# BDAN_TFT.net
KiCad netlist of a schematic drawn in Altium Designer
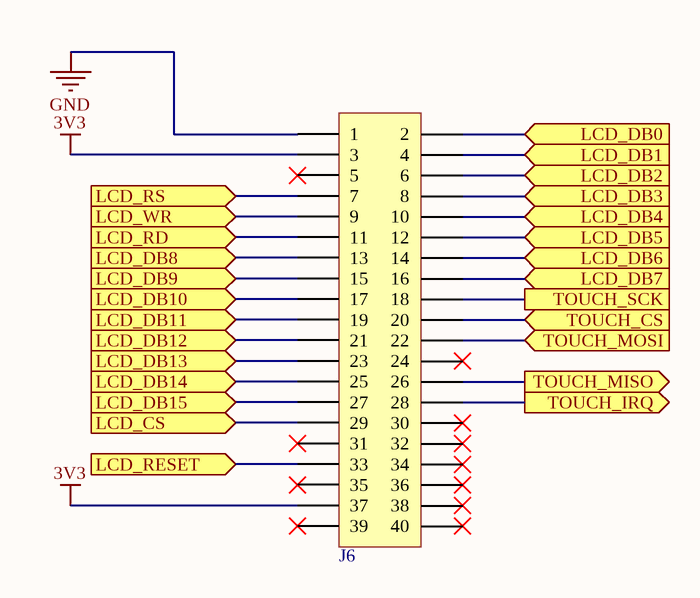
[diagram p0: BDAN_TFT.SchDoc]

(export (version "E")
  (design (tool "Eeschema 10.0.6"))
  (components
    (comp (ref "J6")
      (value "ILI9341")
      (footprint "ILI9341")
      (description "ILI9341-3.2''")
      (fields (field (name "PART NUMBER") "ILI9341-3.2"))
      (libsource (lib "gl_LIB") (part "CON20_2"))
    )
  )
  (nets
    (net (code "1") (name "/LCD_CS") (class "Default")
      (node (ref "J6") (pin "29") (pinfunction "29_29") (pintype "passive"))
    )
    (net (code "2") (name "/LCD_DB0") (class "Default")
      (node (ref "J6") (pin "2") (pinfunction "2_2") (pintype "passive"))
    )
    (net (code "3") (name "/LCD_DB1") (class "Default")
      (node (ref "J6") (pin "4") (pinfunction "4_4") (pintype "passive"))
    )
    (net (code "4") (name "/LCD_DB2") (class "Default")
      (node (ref "J6") (pin "6") (pinfunction "6_6") (pintype "passive"))
    )
    (net (code "5") (name "/LCD_DB3") (class "Default")
      (node (ref "J6") (pin "8") (pinfunction "8_8") (pintype "passive"))
    )
    (net (code "6") (name "/LCD_DB4") (class "Default")
      (node (ref "J6") (pin "10") (pinfunction "10_10") (pintype "passive"))
    )
    (net (code "7") (name "/LCD_DB5") (class "Default")
      (node (ref "J6") (pin "12") (pinfunction "12_12") (pintype "passive"))
    )
    (net (code "8") (name "/LCD_DB6") (class "Default")
      (node (ref "J6") (pin "14") (pinfunction "14_14") (pintype "passive"))
    )
    (net (code "9") (name "/LCD_DB7") (class "Default")
      (node (ref "J6") (pin "16") (pinfunction "16_16") (pintype "passive"))
    )
    (net (code "10") (name "/LCD_DB8") (class "Default")
      (node (ref "J6") (pin "13") (pinfunction "13_13") (pintype "passive"))
    )
    (net (code "11") (name "/LCD_DB9") (class "Default")
      (node (ref "J6") (pin "15") (pinfunction "15_15") (pintype "passive"))
    )
    (net (code "12") (name "/LCD_DB10") (class "Default")
      (node (ref "J6") (pin "17") (pinfunction "17_17") (pintype "passive"))
    )
    (net (code "13") (name "/LCD_DB11") (class "Default")
      (node (ref "J6") (pin "19") (pinfunction "19_19") (pintype "passive"))
    )
    (net (code "14") (name "/LCD_DB12") (class "Default")
      (node (ref "J6") (pin "21") (pinfunction "21_21") (pintype "passive"))
    )
    (net (code "15") (name "/LCD_DB13") (class "Default")
      (node (ref "J6") (pin "23") (pinfunction "23_23") (pintype "passive"))
    )
    (net (code "16") (name "/LCD_DB14") (class "Default")
      (node (ref "J6") (pin "25") (pinfunction "25_25") (pintype "passive"))
    )
    (net (code "17") (name "/LCD_DB15") (class "Default")
      (node (ref "J6") (pin "27") (pinfunction "27_27") (pintype "passive"))
    )
    (net (code "18") (name "/LCD_RD") (class "Default")
      (node (ref "J6") (pin "11") (pinfunction "11_11") (pintype "passive"))
    )
    (net (code "19") (name "/LCD_RESET") (class "Default")
      (node (ref "J6") (pin "33") (pinfunction "33_33") (pintype "passive"))
    )
    (net (code "20") (name "/LCD_RS") (class "Default")
      (node (ref "J6") (pin "7") (pinfunction "7_7") (pintype "passive"))
    )
    (net (code "21") (name "/LCD_WR") (class "Default")
      (node (ref "J6") (pin "9") (pinfunction "9_9") (pintype "passive"))
    )
    (net (code "22") (name "/TOUCH_CS") (class "Default")
      (node (ref "J6") (pin "20") (pinfunction "20_20") (pintype "passive"))
    )
    (net (code "23") (name "/TOUCH_IRQ") (class "Default")
      (node (ref "J6") (pin "28") (pinfunction "28_28") (pintype "passive"))
    )
    (net (code "24") (name "/TOUCH_MISO") (class "Default")
      (node (ref "J6") (pin "26") (pinfunction "26_26") (pintype "passive"))
    )
    (net (code "25") (name "/TOUCH_MOSI") (class "Default")
      (node (ref "J6") (pin "22") (pinfunction "22_22") (pintype "passive"))
    )
    (net (code "26") (name "/TOUCH_SCK") (class "Default")
      (node (ref "J6") (pin "18") (pinfunction "18_18") (pintype "passive"))
    )
    (net (code "27") (name "3V3") (class "Default")
      (node (ref "J6") (pin "3") (pinfunction "3_3") (pintype "passive"))
      (node (ref "J6") (pin "37") (pinfunction "37_37") (pintype "passive"))
    )
    (net (code "28") (name "GND") (class "Default")
      (node (ref "J6") (pin "1") (pinfunction "1_1") (pintype "passive"))
    )
    (net (code "29") (name "unconnected-(J6-Pad5)") (class "Default")
      (node (ref "J6") (pin "5") (pinfunction "5_5") (pintype "passive+no_connect"))
    )
    (net (code "30") (name "unconnected-(J6-Pad24)") (class "Default")
      (node (ref "J6") (pin "24") (pinfunction "24_24") (pintype "passive+no_connect"))
    )
    (net (code "31") (name "unconnected-(J6-Pad30)") (class "Default")
      (node (ref "J6") (pin "30") (pinfunction "30_30") (pintype "passive+no_connect"))
    )
    (net (code "32") (name "unconnected-(J6-Pad31)") (class "Default")
      (node (ref "J6") (pin "31") (pinfunction "31_31") (pintype "passive+no_connect"))
    )
    (net (code "33") (name "unconnected-(J6-Pad32)") (class "Default")
      (node (ref "J6") (pin "32") (pinfunction "32_32") (pintype "passive+no_connect"))
    )
    (net (code "34") (name "unconnected-(J6-Pad34)") (class "Default")
      (node (ref "J6") (pin "34") (pinfunction "34_34") (pintype "passive+no_connect"))
    )
    (net (code "35") (name "unconnected-(J6-Pad35)") (class "Default")
      (node (ref "J6") (pin "35") (pinfunction "35_35") (pintype "passive+no_connect"))
    )
    (net (code "36") (name "unconnected-(J6-Pad36)") (class "Default")
      (node (ref "J6") (pin "36") (pinfunction "36_36") (pintype "passive+no_connect"))
    )
    (net (code "37") (name "unconnected-(J6-Pad38)") (class "Default")
      (node (ref "J6") (pin "38") (pinfunction "38_38") (pintype "passive+no_connect"))
    )
    (net (code "38") (name "unconnected-(J6-Pad39)") (class "Default")
      (node (ref "J6") (pin "39") (pinfunction "39_39") (pintype "passive+no_connect"))
    )
    (net (code "39") (name "unconnected-(J6-Pad40)") (class "Default")
      (node (ref "J6") (pin "40") (pinfunction "40_40") (pintype "passive+no_connect"))
    )
  )
)
